# PDMschemC-Car2018.net
KiCad netlist of a schematic drawn in EAGLE
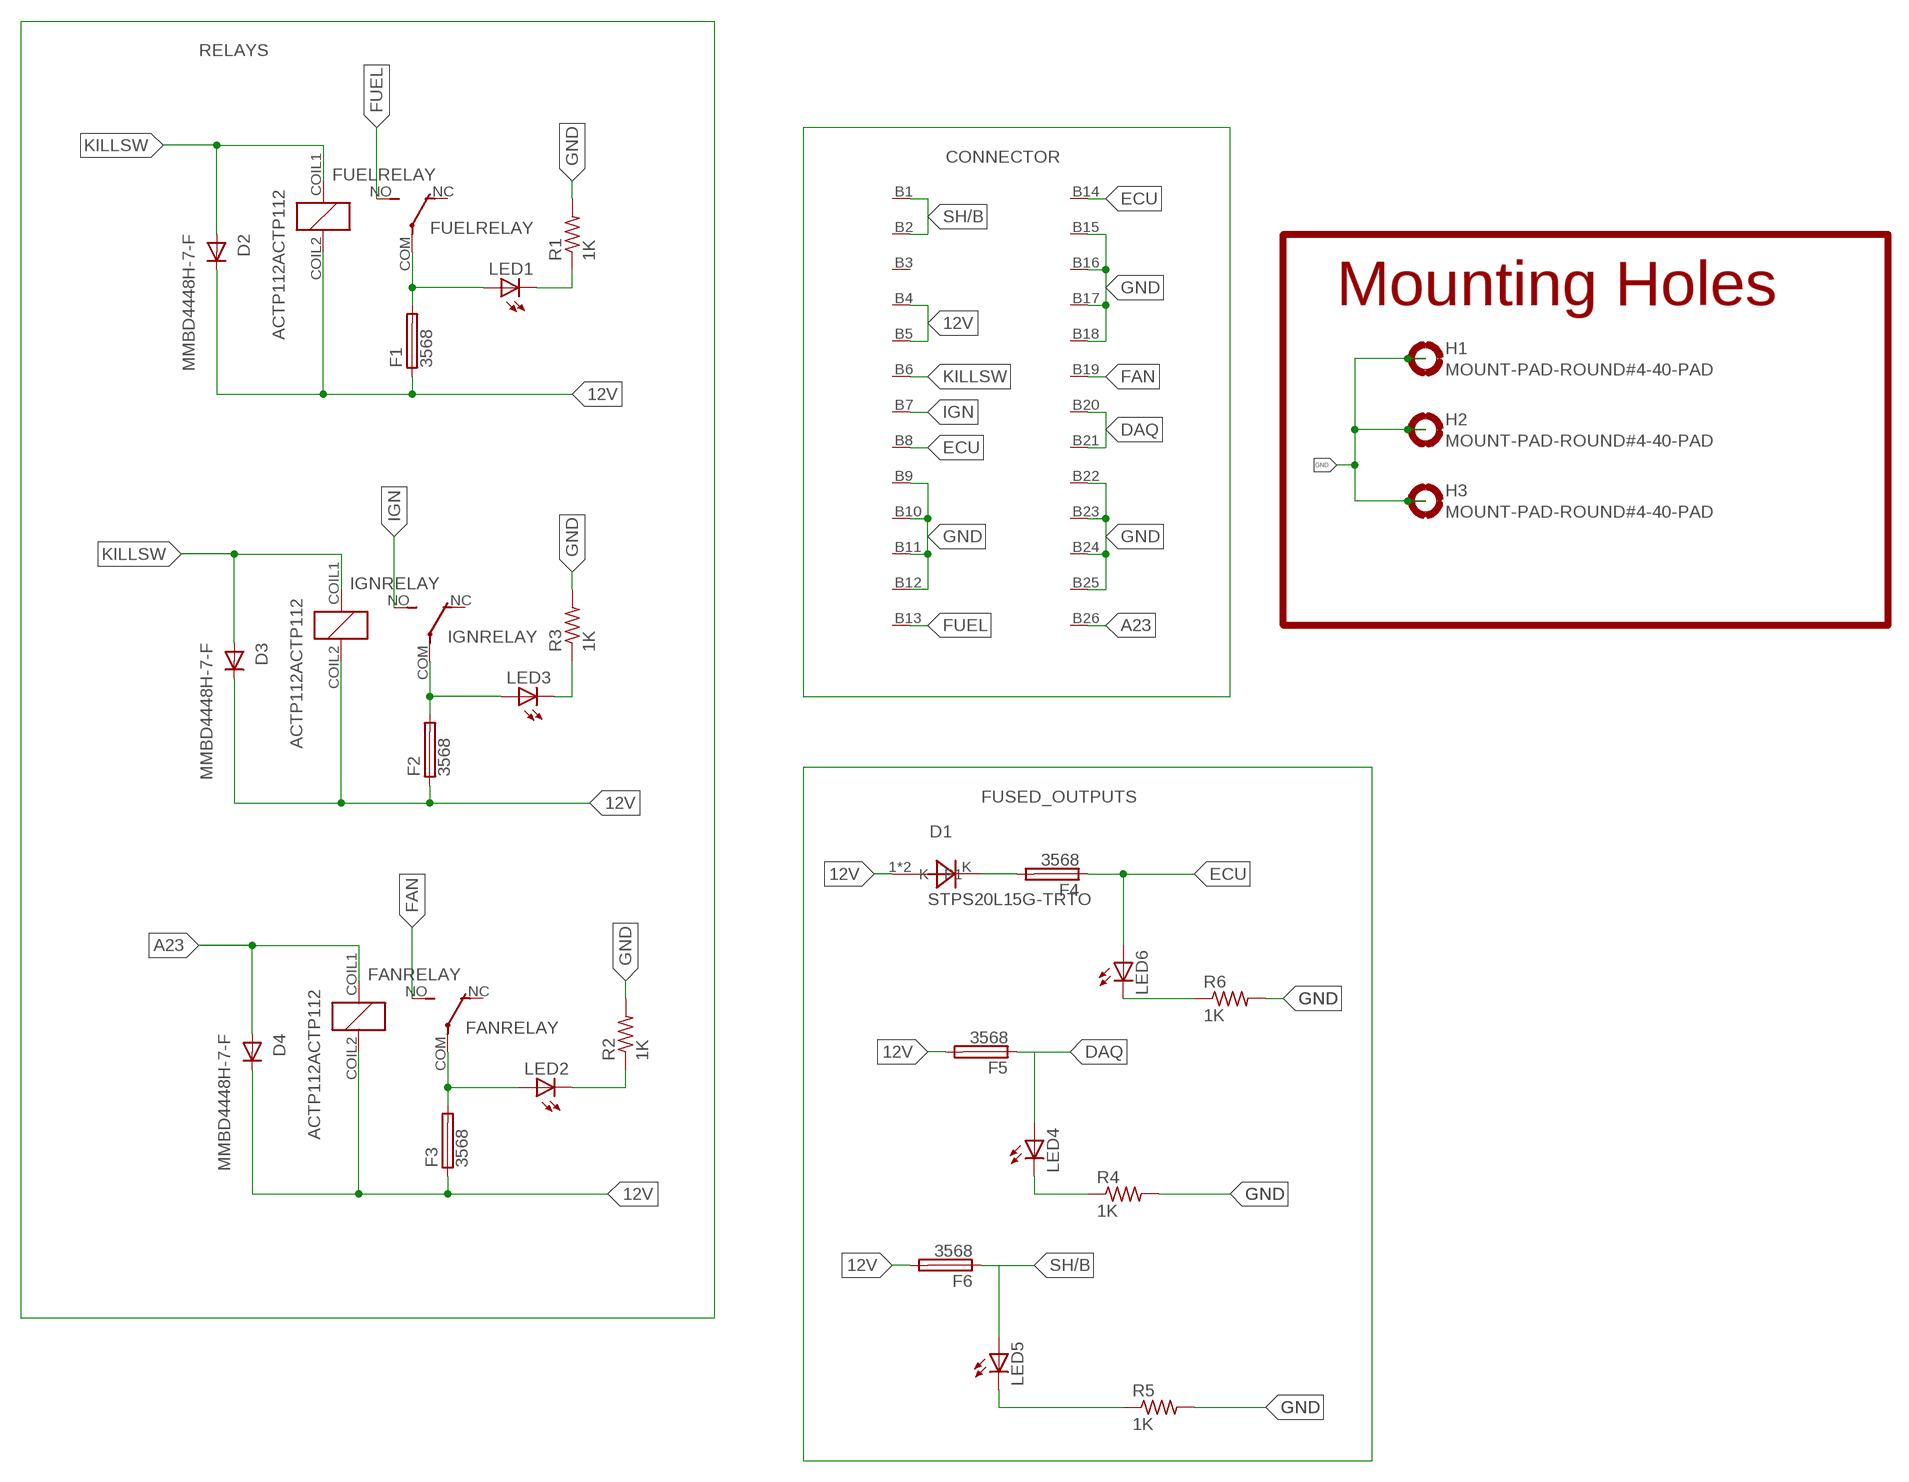
[diagram p0: schematic, sheet 1]

(export (version "E")
  (design (tool "Eeschema 10.0.6"))
  (components
    (comp (ref "D1")
      (value "STPS20L15G-TRTO")
      (footprint "eagle-import:TO-262DIODE")
      (libsource (lib "eagle-import") (part "STPS20L15G-TRTO"))
    )
    (comp (ref "D2")
      (value "MMBD4448H-7-F")
      (footprint "eagle-import:SOT23-3")
      (libsource (lib "eagle-import") (part "MMBD4448H-7-F"))
    )
    (comp (ref "D3")
      (value "MMBD4448H-7-F")
      (footprint "eagle-import:SOT23-3")
      (libsource (lib "eagle-import") (part "MMBD4448H-7-F"))
    )
    (comp (ref "D4")
      (value "MMBD4448H-7-F")
      (footprint "eagle-import:SOT23-3")
      (libsource (lib "eagle-import") (part "MMBD4448H-7-F"))
    )
    (comp (ref "F1")
      (value "3568")
      (footprint "eagle-import:3568")
      (libsource (lib "eagle-import") (part "3568"))
    )
    (comp (ref "F2")
      (value "3568")
      (footprint "eagle-import:3568")
      (libsource (lib "eagle-import") (part "3568"))
    )
    (comp (ref "F3")
      (value "3568")
      (footprint "eagle-import:3568")
      (libsource (lib "eagle-import") (part "3568"))
    )
    (comp (ref "F4")
      (value "3568")
      (footprint "eagle-import:3568")
      (libsource (lib "eagle-import") (part "3568"))
    )
    (comp (ref "F5")
      (value "3568")
      (footprint "eagle-import:3568")
      (libsource (lib "eagle-import") (part "3568"))
    )
    (comp (ref "F6")
      (value "3568")
      (footprint "eagle-import:3568")
      (libsource (lib "eagle-import") (part "3568"))
    )
    (comp (ref "FANRELAY")
      (value "ACTP112ACTP112")
      (footprint "eagle-import:ACTP112")
      (libsource (lib "eagle-import") (part "ACTP112ACTP112"))
    )
    (comp (ref "FUELRELAY")
      (value "ACTP112ACTP112")
      (footprint "eagle-import:ACTP112")
      (libsource (lib "eagle-import") (part "ACTP112ACTP112"))
    )
    (comp (ref "H1")
      (value "MOUNT-PAD-ROUND#4-40-PAD")
      (footprint "eagle-import:#4-40-PAD-ROUND")
      (libsource (lib "eagle-import") (part "MOUNT-PAD-ROUND#4-40-PAD"))
    )
    (comp (ref "H2")
      (value "MOUNT-PAD-ROUND#4-40-PAD")
      (footprint "eagle-import:#4-40-PAD-ROUND")
      (libsource (lib "eagle-import") (part "MOUNT-PAD-ROUND#4-40-PAD"))
    )
    (comp (ref "H3")
      (value "MOUNT-PAD-ROUND#4-40-PAD")
      (footprint "eagle-import:#4-40-PAD-ROUND")
      (libsource (lib "eagle-import") (part "MOUNT-PAD-ROUND#4-40-PAD"))
    )
    (comp (ref "IGNRELAY")
      (value "ACTP112ACTP112")
      (footprint "eagle-import:ACTP112")
      (libsource (lib "eagle-import") (part "ACTP112ACTP112"))
    )
    (comp (ref "LED1")
      (value "LEDCHIPLED_0805")
      (footprint "eagle-import:CHIPLED_0805")
      (libsource (lib "eagle-import") (part "LEDCHIPLED_0805"))
    )
    (comp (ref "LED2")
      (value "LEDCHIPLED_0805")
      (footprint "eagle-import:CHIPLED_0805")
      (libsource (lib "eagle-import") (part "LEDCHIPLED_0805"))
    )
    (comp (ref "LED3")
      (value "LEDCHIPLED_0805")
      (footprint "eagle-import:CHIPLED_0805")
      (libsource (lib "eagle-import") (part "LEDCHIPLED_0805"))
    )
    (comp (ref "LED4")
      (value "LEDCHIPLED_0805")
      (footprint "eagle-import:CHIPLED_0805")
      (libsource (lib "eagle-import") (part "LEDCHIPLED_0805"))
    )
    (comp (ref "LED5")
      (value "LEDCHIPLED_0805")
      (footprint "eagle-import:CHIPLED_0805")
      (libsource (lib "eagle-import") (part "LEDCHIPLED_0805"))
    )
    (comp (ref "LED6")
      (value "LEDCHIPLED_0805")
      (footprint "eagle-import:CHIPLED_0805")
      (libsource (lib "eagle-import") (part "LEDCHIPLED_0805"))
    )
    (comp (ref "R1")
      (value "1K")
      (footprint "eagle-import:R0805")
      (libsource (lib "eagle-import") (part "R-US_R0805"))
    )
    (comp (ref "R2")
      (value "1K")
      (footprint "eagle-import:R0805")
      (libsource (lib "eagle-import") (part "R-US_R0805"))
    )
    (comp (ref "R3")
      (value "1K")
      (footprint "eagle-import:R0805")
      (libsource (lib "eagle-import") (part "R-US_R0805"))
    )
    (comp (ref "R4")
      (value "1K")
      (footprint "eagle-import:R0805")
      (libsource (lib "eagle-import") (part "R-US_R0805"))
    )
    (comp (ref "R5")
      (value "1K")
      (footprint "eagle-import:R0805")
      (libsource (lib "eagle-import") (part "R-US_R0805"))
    )
    (comp (ref "R6")
      (value "1K")
      (footprint "eagle-import:R0805")
      (libsource (lib "eagle-import") (part "R-US_R0805"))
    )
    (comp (ref "U$1")
      (value "SUPERSEAL1.0_26POS")
      (footprint "eagle-import:SUPERSEAL1.0_26POS")
      (libsource (lib "eagle-import") (part "SUPERSEAL1.0_26POS"))
    )
  )
  (nets
    (net (code "4") (name "12V") (class "Default")
      (node (ref "D1") (pin "1") (pinfunction "P1_1") (pintype "bidirectional"))
      (node (ref "D1") (pin "2") (pinfunction "P1_2") (pintype "bidirectional"))
      (node (ref "D2") (pin "3") (pinfunction "C_3") (pintype "passive"))
      (node (ref "D3") (pin "3") (pinfunction "C_3") (pintype "passive"))
      (node (ref "D4") (pin "3") (pinfunction "C_3") (pintype "passive"))
      (node (ref "F1") (pin "1") (pinfunction "1_1") (pintype "passive"))
      (node (ref "F1") (pin "2") (pinfunction "1_2") (pintype "passive"))
      (node (ref "F2") (pin "1") (pinfunction "1_1") (pintype "passive"))
      (node (ref "F2") (pin "2") (pinfunction "1_2") (pintype "passive"))
      (node (ref "F3") (pin "1") (pinfunction "1_1") (pintype "passive"))
      (node (ref "F3") (pin "2") (pinfunction "1_2") (pintype "passive"))
      (node (ref "F5") (pin "3") (pinfunction "2_3") (pintype "passive"))
      (node (ref "F5") (pin "4") (pinfunction "2_4") (pintype "passive"))
      (node (ref "F6") (pin "3") (pinfunction "2_3") (pintype "passive"))
      (node (ref "F6") (pin "4") (pinfunction "2_4") (pintype "passive"))
      (node (ref "FANRELAY") (pin "COIL2") (pinfunction "COIL2_COIL2") (pintype "passive"))
      (node (ref "FUELRELAY") (pin "COIL2") (pinfunction "COIL2_COIL2") (pintype "passive"))
      (node (ref "IGNRELAY") (pin "COIL2") (pinfunction "COIL2_COIL2") (pintype "passive"))
      (node (ref "U$1") (pin "B4") (pinfunction "B4_B4") (pintype "bidirectional"))
      (node (ref "U$1") (pin "B5") (pinfunction "B5_B5") (pintype "bidirectional"))
    )
    (net (code "5") (name "A23") (class "Default")
      (node (ref "D4") (pin "1") (pinfunction "A_1") (pintype "passive"))
      (node (ref "FANRELAY") (pin "COIL1") (pinfunction "COIL1_COIL1") (pintype "passive"))
      (node (ref "U$1") (pin "B26") (pinfunction "B26_B26") (pintype "bidirectional"))
    )
    (net (code "6") (name "DAQ") (class "Default")
      (node (ref "F5") (pin "1") (pinfunction "1_1") (pintype "passive"))
      (node (ref "F5") (pin "2") (pinfunction "1_2") (pintype "passive"))
      (node (ref "LED4") (pin "A") (pinfunction "A_A") (pintype "passive"))
      (node (ref "U$1") (pin "B20") (pinfunction "B20_B20") (pintype "bidirectional"))
      (node (ref "U$1") (pin "B21") (pinfunction "B21_B21") (pintype "bidirectional"))
    )
    (net (code "7") (name "ECU") (class "Default")
      (node (ref "F4") (pin "1") (pinfunction "1_1") (pintype "passive"))
      (node (ref "F4") (pin "2") (pinfunction "1_2") (pintype "passive"))
      (node (ref "LED6") (pin "A") (pinfunction "A_A") (pintype "passive"))
      (node (ref "U$1") (pin "B14") (pinfunction "B14_B14") (pintype "bidirectional"))
      (node (ref "U$1") (pin "B8") (pinfunction "B8_B8") (pintype "bidirectional"))
    )
    (net (code "8") (name "FAN") (class "Default")
      (node (ref "FANRELAY") (pin "NO") (pinfunction "NO_NO") (pintype "passive"))
      (node (ref "U$1") (pin "B19") (pinfunction "B19_B19") (pintype "bidirectional"))
    )
    (net (code "9") (name "FUEL") (class "Default")
      (node (ref "FUELRELAY") (pin "NO") (pinfunction "NO_NO") (pintype "passive"))
      (node (ref "U$1") (pin "B13") (pinfunction "B13_B13") (pintype "bidirectional"))
    )
    (net (code "10") (name "GND") (class "Default")
      (node (ref "H1") (pin "P$1") (pinfunction "MOUNT_P$1") (pintype "passive"))
      (node (ref "H2") (pin "P$1") (pinfunction "MOUNT_P$1") (pintype "passive"))
      (node (ref "H3") (pin "P$1") (pinfunction "MOUNT_P$1") (pintype "passive"))
      (node (ref "R1") (pin "2") (pinfunction "2_2") (pintype "passive"))
      (node (ref "R2") (pin "2") (pinfunction "2_2") (pintype "passive"))
      (node (ref "R3") (pin "2") (pinfunction "2_2") (pintype "passive"))
      (node (ref "R4") (pin "2") (pinfunction "2_2") (pintype "passive"))
      (node (ref "R5") (pin "2") (pinfunction "2_2") (pintype "passive"))
      (node (ref "R6") (pin "2") (pinfunction "2_2") (pintype "passive"))
      (node (ref "U$1") (pin "B10") (pinfunction "B10_B10") (pintype "bidirectional"))
      (node (ref "U$1") (pin "B11") (pinfunction "B11_B11") (pintype "bidirectional"))
      (node (ref "U$1") (pin "B12") (pinfunction "B12_B12") (pintype "bidirectional"))
      (node (ref "U$1") (pin "B15") (pinfunction "B15_B15") (pintype "bidirectional"))
      (node (ref "U$1") (pin "B16") (pinfunction "B16_B16") (pintype "bidirectional"))
      (node (ref "U$1") (pin "B17") (pinfunction "B17_B17") (pintype "bidirectional"))
      (node (ref "U$1") (pin "B18") (pinfunction "B18_B18") (pintype "bidirectional"))
      (node (ref "U$1") (pin "B22") (pinfunction "B22_B22") (pintype "bidirectional"))
      (node (ref "U$1") (pin "B23") (pinfunction "B23_B23") (pintype "bidirectional"))
      (node (ref "U$1") (pin "B24") (pinfunction "B24_B24") (pintype "bidirectional"))
      (node (ref "U$1") (pin "B25") (pinfunction "B25_B25") (pintype "bidirectional"))
      (node (ref "U$1") (pin "B9") (pinfunction "B9_B9") (pintype "bidirectional"))
    )
    (net (code "11") (name "IGN") (class "Default")
      (node (ref "IGNRELAY") (pin "NO") (pinfunction "NO_NO") (pintype "passive"))
      (node (ref "U$1") (pin "B7") (pinfunction "B7_B7") (pintype "bidirectional"))
    )
    (net (code "12") (name "KILLSW") (class "Default")
      (node (ref "D2") (pin "1") (pinfunction "A_1") (pintype "passive"))
      (node (ref "D3") (pin "1") (pinfunction "A_1") (pintype "passive"))
      (node (ref "FUELRELAY") (pin "COIL1") (pinfunction "COIL1_COIL1") (pintype "passive"))
      (node (ref "IGNRELAY") (pin "COIL1") (pinfunction "COIL1_COIL1") (pintype "passive"))
      (node (ref "U$1") (pin "B6") (pinfunction "B6_B6") (pintype "bidirectional"))
    )
    (net (code "13") (name "Net-(D1-PadK)") (class "Default")
      (node (ref "D1") (pin "K") (pinfunction "K_K") (pintype "bidirectional"))
      (node (ref "F4") (pin "3") (pinfunction "2_3") (pintype "passive"))
      (node (ref "F4") (pin "4") (pinfunction "2_4") (pintype "passive"))
    )
    (net (code "14") (name "Net-(F1-2-Pad3)") (class "Default")
      (node (ref "F1") (pin "3") (pinfunction "2_3") (pintype "passive"))
      (node (ref "F1") (pin "4") (pinfunction "2_4") (pintype "passive"))
      (node (ref "FUELRELAY") (pin "COM") (pinfunction "COM_COM") (pintype "passive"))
      (node (ref "LED1") (pin "A") (pinfunction "A_A") (pintype "passive"))
    )
    (net (code "15") (name "Net-(F2-2-Pad3)") (class "Default")
      (node (ref "F2") (pin "3") (pinfunction "2_3") (pintype "passive"))
      (node (ref "F2") (pin "4") (pinfunction "2_4") (pintype "passive"))
      (node (ref "IGNRELAY") (pin "COM") (pinfunction "COM_COM") (pintype "passive"))
      (node (ref "LED3") (pin "A") (pinfunction "A_A") (pintype "passive"))
    )
    (net (code "16") (name "Net-(F3-2-Pad3)") (class "Default")
      (node (ref "F3") (pin "3") (pinfunction "2_3") (pintype "passive"))
      (node (ref "F3") (pin "4") (pinfunction "2_4") (pintype "passive"))
      (node (ref "FANRELAY") (pin "COM") (pinfunction "COM_COM") (pintype "passive"))
      (node (ref "LED2") (pin "A") (pinfunction "A_A") (pintype "passive"))
    )
    (net (code "17") (name "Net-(LED1-PadC)") (class "Default")
      (node (ref "LED1") (pin "C") (pinfunction "C_C") (pintype "passive"))
      (node (ref "R1") (pin "1") (pinfunction "1_1") (pintype "passive"))
    )
    (net (code "18") (name "Net-(LED2-PadC)") (class "Default")
      (node (ref "LED2") (pin "C") (pinfunction "C_C") (pintype "passive"))
      (node (ref "R2") (pin "1") (pinfunction "1_1") (pintype "passive"))
    )
    (net (code "19") (name "Net-(LED3-PadC)") (class "Default")
      (node (ref "LED3") (pin "C") (pinfunction "C_C") (pintype "passive"))
      (node (ref "R3") (pin "1") (pinfunction "1_1") (pintype "passive"))
    )
    (net (code "20") (name "Net-(LED4-PadC)") (class "Default")
      (node (ref "LED4") (pin "C") (pinfunction "C_C") (pintype "passive"))
      (node (ref "R4") (pin "1") (pinfunction "1_1") (pintype "passive"))
    )
    (net (code "21") (name "Net-(LED5-PadC)") (class "Default")
      (node (ref "LED5") (pin "C") (pinfunction "C_C") (pintype "passive"))
      (node (ref "R5") (pin "1") (pinfunction "1_1") (pintype "passive"))
    )
    (net (code "22") (name "Net-(LED6-PadC)") (class "Default")
      (node (ref "LED6") (pin "C") (pinfunction "C_C") (pintype "passive"))
      (node (ref "R6") (pin "1") (pinfunction "1_1") (pintype "passive"))
    )
    (net (code "23") (name "SH{slash}B") (class "Default")
      (node (ref "F6") (pin "1") (pinfunction "1_1") (pintype "passive"))
      (node (ref "F6") (pin "2") (pinfunction "1_2") (pintype "passive"))
      (node (ref "LED5") (pin "A") (pinfunction "A_A") (pintype "passive"))
      (node (ref "U$1") (pin "B1") (pinfunction "B1_B1") (pintype "bidirectional"))
      (node (ref "U$1") (pin "B2") (pinfunction "B2_B2") (pintype "bidirectional"))
    )
    (net (code "24") (name "unconnected-(FANRELAY-PadNC)") (class "Default")
      (node (ref "FANRELAY") (pin "NC") (pinfunction "NC_NC") (pintype "passive"))
    )
    (net (code "25") (name "unconnected-(FUELRELAY-PadNC)") (class "Default")
      (node (ref "FUELRELAY") (pin "NC") (pinfunction "NC_NC") (pintype "passive"))
    )
    (net (code "26") (name "unconnected-(IGNRELAY-PadNC)") (class "Default")
      (node (ref "IGNRELAY") (pin "NC") (pinfunction "NC_NC") (pintype "passive"))
    )
    (net (code "27") (name "unconnected-(U$1-PadB3)") (class "Default")
      (node (ref "U$1") (pin "B3") (pinfunction "B3_B3") (pintype "bidirectional"))
    )
  )
)
